# M_B_adapter_414.net
KiCad netlist of a schematic drawn in EAGLE
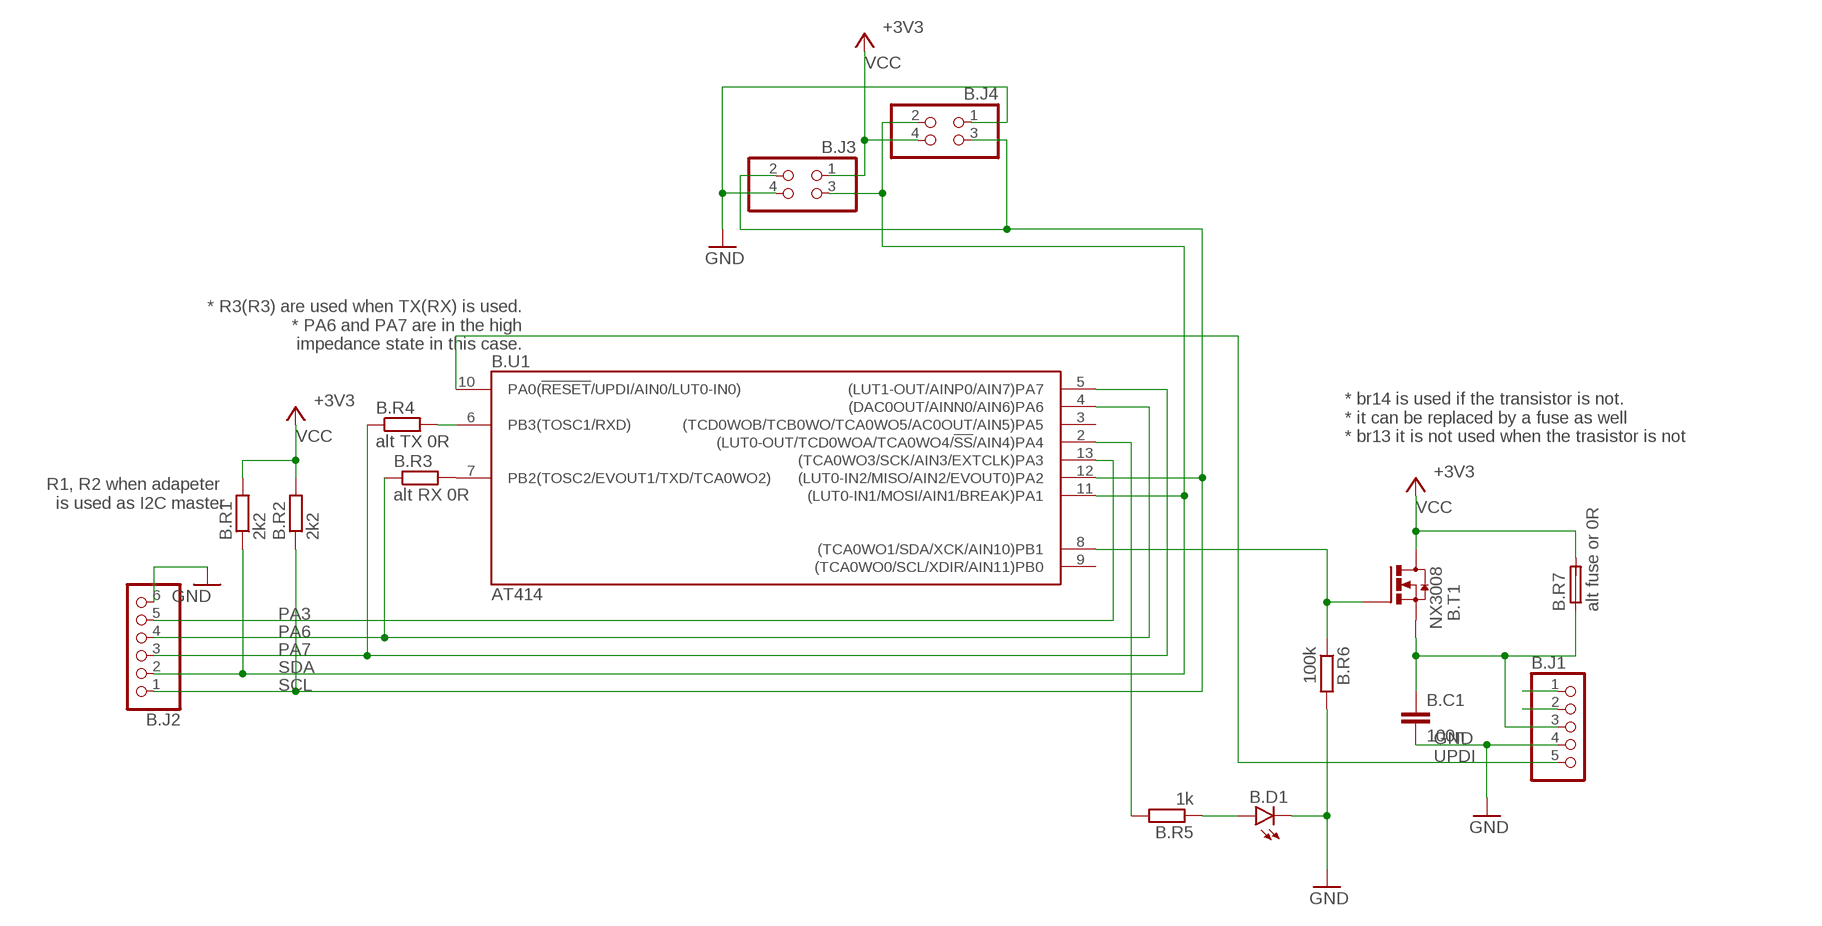
[diagram p0: schematic, sheet 1]

(export (version "E")
  (design (tool "Eeschema 10.0.6"))
  (components
    (comp (ref "B.C1")
      (value "100n")
      (footprint "eagle-import:C0603")
      (libsource (lib "eagle-import") (part "C-EUC0603"))
    )
    (comp (ref "B.D1")
      (value "LEDCHIP-LED0603")
      (footprint "eagle-import:CHIP-LED0603")
      (libsource (lib "eagle-import") (part "LEDCHIP-LED0603"))
    )
    (comp (ref "B.J1")
      (value "PINHD-1X5")
      (footprint "eagle-import:1X05")
      (libsource (lib "eagle-import") (part "PINHD-1X5"))
    )
    (comp (ref "B.J2")
      (value "PINHD-1X6")
      (footprint "eagle-import:1X06")
      (libsource (lib "eagle-import") (part "PINHD-1X6"))
    )
    (comp (ref "B.J3")
      (value "PINHD-2X2")
      (footprint "eagle-import:2X02")
      (libsource (lib "eagle-import") (part "PINHD-2X2"))
    )
    (comp (ref "B.J4")
      (value "PINHD-2X2")
      (footprint "eagle-import:2X02")
      (libsource (lib "eagle-import") (part "PINHD-2X2"))
    )
    (comp (ref "B.R1")
      (value "2k2")
      (footprint "eagle-import:R0603")
      (libsource (lib "eagle-import") (part "R-EU_R0603"))
    )
    (comp (ref "B.R2")
      (value "2k2")
      (footprint "eagle-import:R0603")
      (libsource (lib "eagle-import") (part "R-EU_R0603"))
    )
    (comp (ref "B.R3")
      (value "alt RX 0R")
      (footprint "eagle-import:R0603")
      (libsource (lib "eagle-import") (part "R-EU_R0603"))
    )
    (comp (ref "B.R4")
      (value "alt TX 0R")
      (footprint "eagle-import:R0603")
      (libsource (lib "eagle-import") (part "R-EU_R0603"))
    )
    (comp (ref "B.R5")
      (value "1k")
      (footprint "eagle-import:R0603")
      (libsource (lib "eagle-import") (part "R-EU_R0603"))
    )
    (comp (ref "B.R6")
      (value "100k")
      (footprint "eagle-import:R0603")
      (libsource (lib "eagle-import") (part "R-EU_R0603"))
    )
    (comp (ref "B.R7")
      (value "alt fuse or 0R")
      (footprint "eagle-import:FUSE")
      (libsource (lib "eagle-import") (part "FUSE"))
    )
    (comp (ref "B.T1")
      (value "NX3008")
      (footprint "eagle-import:SO23")
      (libsource (lib "eagle-import") (part "N-MOSFET"))
    )
    (comp (ref "B.U1")
      (value "AT414")
      (footprint "eagle-import:SO14")
      (libsource (lib "eagle-import") (part "ATTINY14-SSN4"))
    )
  )
  (nets
    (net (code "1") (name "+3V3") (class "Default")
      (node (ref "B.J3") (pin "1") (pinfunction "1_1") (pintype "passive"))
      (node (ref "B.J4") (pin "4") (pinfunction "4_4") (pintype "passive"))
      (node (ref "B.R1") (pin "2") (pinfunction "2_2") (pintype "passive"))
      (node (ref "B.R2") (pin "2") (pinfunction "2_2") (pintype "passive"))
      (node (ref "B.R7") (pin "2") (pinfunction "2_2") (pintype "passive"))
      (node (ref "B.T1") (pin "D") (pinfunction "D_D") (pintype "passive"))
    )
    (net (code "2") (name "/PA3") (class "Default")
      (node (ref "B.J2") (pin "5") (pinfunction "5_5") (pintype "passive"))
      (node (ref "B.U1") (pin "13") (pinfunction "(TCA0WO3/SCK/AIN3/EXTCLK)PA3_13") (pintype "bidirectional"))
    )
    (net (code "3") (name "/PA6") (class "Default")
      (node (ref "B.J2") (pin "4") (pinfunction "4_4") (pintype "passive"))
      (node (ref "B.R3") (pin "1") (pinfunction "1_1") (pintype "passive"))
      (node (ref "B.U1") (pin "4") (pinfunction "(DAC0OUT/AINN0/AIN6)PA6_4") (pintype "bidirectional"))
    )
    (net (code "4") (name "/PA7") (class "Default")
      (node (ref "B.J2") (pin "3") (pinfunction "3_3") (pintype "passive"))
      (node (ref "B.R4") (pin "1") (pinfunction "1_1") (pintype "passive"))
      (node (ref "B.U1") (pin "5") (pinfunction "(LUT1-OUT/AINP0/AIN7)PA7_5") (pintype "bidirectional"))
    )
    (net (code "5") (name "/SCL") (class "Default")
      (node (ref "B.J2") (pin "1") (pinfunction "1_1") (pintype "passive"))
      (node (ref "B.J3") (pin "2") (pinfunction "2_2") (pintype "passive"))
      (node (ref "B.J4") (pin "3") (pinfunction "3_3") (pintype "passive"))
      (node (ref "B.R2") (pin "1") (pinfunction "1_1") (pintype "passive"))
      (node (ref "B.U1") (pin "12") (pinfunction "(LUT0-IN2/MISO/AIN2/EVOUT0)PA2_12") (pintype "bidirectional"))
    )
    (net (code "6") (name "/SDA") (class "Default")
      (node (ref "B.J2") (pin "2") (pinfunction "2_2") (pintype "passive"))
      (node (ref "B.J3") (pin "3") (pinfunction "3_3") (pintype "passive"))
      (node (ref "B.J4") (pin "2") (pinfunction "2_2") (pintype "passive"))
      (node (ref "B.R1") (pin "1") (pinfunction "1_1") (pintype "passive"))
      (node (ref "B.U1") (pin "11") (pinfunction "(LUT0-IN1/MOSI/AIN1/BREAK)PA1_11") (pintype "bidirectional"))
    )
    (net (code "7") (name "/UPDI") (class "Default")
      (node (ref "B.J1") (pin "5") (pinfunction "5_5") (pintype "passive"))
      (node (ref "B.U1") (pin "10") (pinfunction "PA0(~{RESET}/UPDI/AIN0/LUT0-IN0)_10") (pintype "bidirectional"))
    )
    (net (code "8") (name "GND") (class "Default")
      (node (ref "B.C1") (pin "2") (pinfunction "2_2") (pintype "passive"))
      (node (ref "B.D1") (pin "C1") (pinfunction "C_C1") (pintype "passive"))
      (node (ref "B.J1") (pin "4") (pinfunction "4_4") (pintype "passive"))
      (node (ref "B.J2") (pin "6") (pinfunction "6_6") (pintype "passive"))
      (node (ref "B.J3") (pin "4") (pinfunction "4_4") (pintype "passive"))
      (node (ref "B.J4") (pin "1") (pinfunction "1_1") (pintype "passive"))
      (node (ref "B.R6") (pin "2") (pinfunction "2_2") (pintype "passive"))
    )
    (net (code "9") (name "Net-(B.C1-Pad1)") (class "Default")
      (node (ref "B.C1") (pin "1") (pinfunction "1_1") (pintype "passive"))
      (node (ref "B.J1") (pin "3") (pinfunction "3_3") (pintype "passive"))
      (node (ref "B.R7") (pin "1") (pinfunction "1_1") (pintype "passive"))
      (node (ref "B.T1") (pin "S") (pinfunction "S_S") (pintype "passive"))
    )
    (net (code "10") (name "Net-(B.D1-A)") (class "Default")
      (node (ref "B.D1") (pin "A1") (pinfunction "A_A1") (pintype "passive"))
      (node (ref "B.R5") (pin "1") (pinfunction "1_1") (pintype "passive"))
    )
    (net (code "11") (name "Net-(B.U1A-(LUT0-OUT{slash}TCD0WOA{slash}TCA0WO4{slash}~{SS}{slash}AIN4)PA4)") (class "Default")
      (node (ref "B.R5") (pin "2") (pinfunction "2_2") (pintype "passive"))
      (node (ref "B.U1") (pin "2") (pinfunction "(LUT0-OUT/TCD0WOA/TCA0WO4/~{SS}/AIN4)PA4_2") (pintype "bidirectional"))
    )
    (net (code "12") (name "Net-(B.U1A-(TCA0WO1{slash}SDA{slash}XCK{slash}AIN10)PB1)") (class "Default")
      (node (ref "B.R6") (pin "1") (pinfunction "1_1") (pintype "passive"))
      (node (ref "B.T1") (pin "G") (pinfunction "G_G") (pintype "passive"))
      (node (ref "B.U1") (pin "8") (pinfunction "(TCA0WO1/SDA/XCK/AIN10)PB1_8") (pintype "bidirectional"))
    )
    (net (code "13") (name "Net-(B.U1A-PB2(TOSC2{slash}EVOUT1{slash}TXD{slash}TCA0WO2))") (class "Default")
      (node (ref "B.R3") (pin "2") (pinfunction "2_2") (pintype "passive"))
      (node (ref "B.U1") (pin "7") (pinfunction "PB2(TOSC2/EVOUT1/TXD/TCA0WO2)_7") (pintype "bidirectional"))
    )
    (net (code "14") (name "Net-(B.U1A-PB3(TOSC1{slash}RXD))") (class "Default")
      (node (ref "B.R4") (pin "2") (pinfunction "2_2") (pintype "passive"))
      (node (ref "B.U1") (pin "6") (pinfunction "PB3(TOSC1/RXD)_6") (pintype "bidirectional"))
    )
    (net (code "15") (name "unconnected-(B.J1-Pad1)") (class "Default")
      (node (ref "B.J1") (pin "1") (pinfunction "1_1") (pintype "passive"))
    )
    (net (code "16") (name "unconnected-(B.J1-Pad2)") (class "Default")
      (node (ref "B.J1") (pin "2") (pinfunction "2_2") (pintype "passive"))
    )
    (net (code "17") (name "unconnected-(B.U1A-(TCA0WO0{slash}SCL{slash}XDIR{slash}AIN11)PB0-Pad9)") (class "Default")
      (node (ref "B.U1") (pin "9") (pinfunction "(TCA0WO0/SCL/XDIR/AIN11)PB0_9") (pintype "bidirectional"))
    )
    (net (code "18") (name "unconnected-(B.U1A-(TCD0WOB{slash}TCB0WO{slash}TCA0WO5{slash}AC0OUT{slash}AIN5)PA5-Pad3)") (class "Default")
      (node (ref "B.U1") (pin "3") (pinfunction "(TCD0WOB/TCB0WO/TCA0WO5/AC0OUT/AIN5)PA5_3") (pintype "bidirectional"))
    )
  )
)
